# robot_board.net
KiCad netlist of a schematic drawn in EAGLE
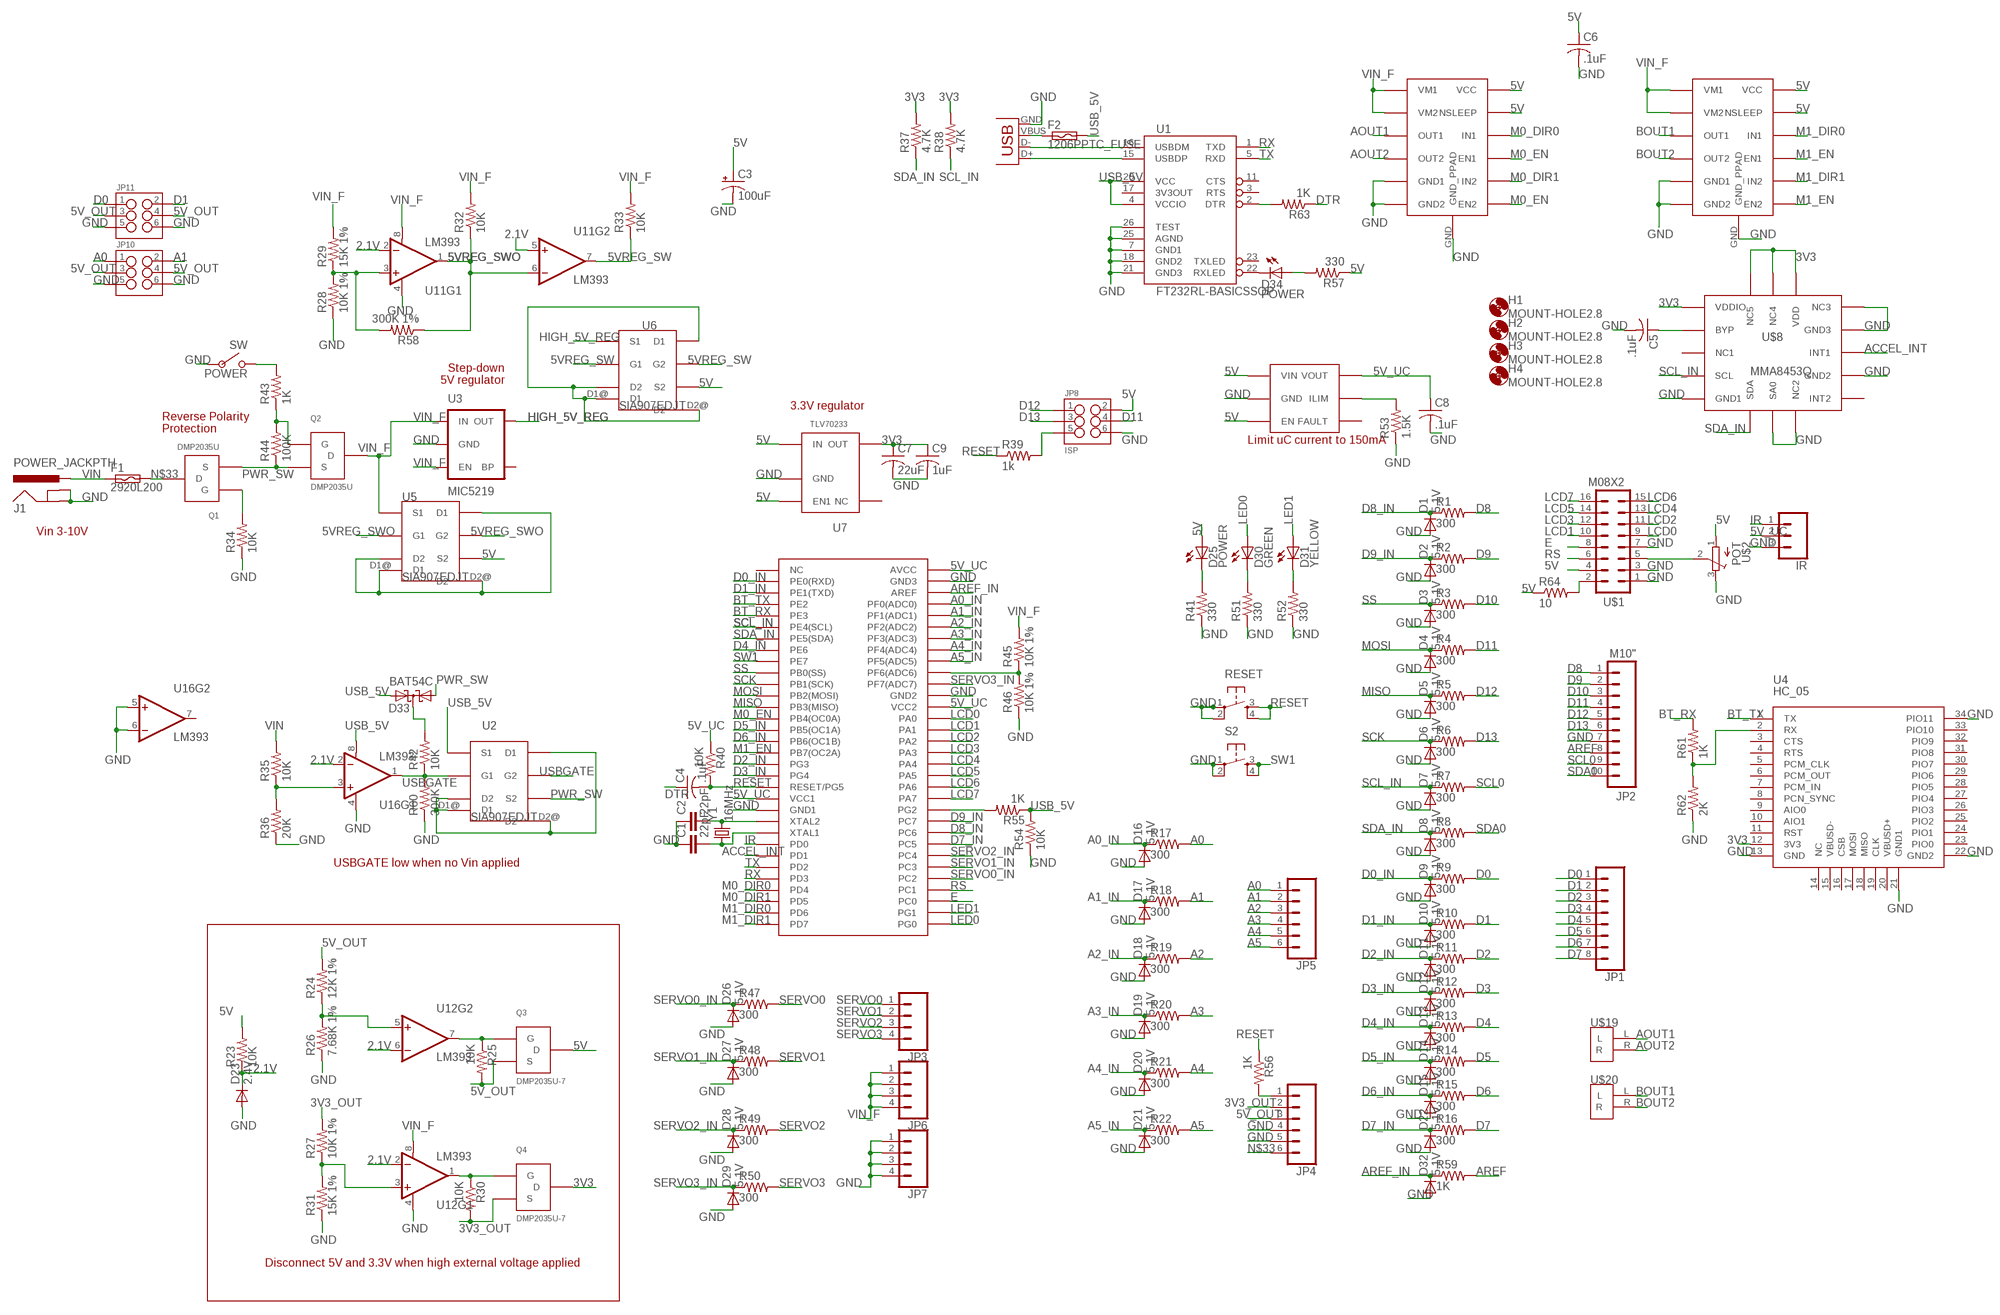
[diagram p0: schematic, sheet 1]

(export (version "E")
  (design (tool "Eeschema 10.0.6"))
  (components
    (comp (ref "C1")
      (value "22pF")
      (footprint "eagle-import:0805")
      (libsource (lib "eagle-import") (part "CAP0805"))
    )
    (comp (ref "C2")
      (value "22pF")
      (footprint "eagle-import:0805")
      (libsource (lib "eagle-import") (part "CAP0805"))
    )
    (comp (ref "C3")
      (value "100uF")
      (footprint "eagle-import:PANASONIC_D")
      (libsource (lib "eagle-import") (part "CAP_POLD"))
    )
    (comp (ref "C4")
      (value ".1uF")
      (footprint "eagle-import:C1206")
      (libsource (lib "eagle-import") (part "C-USC1206"))
    )
    (comp (ref "C5")
      (value ".1uF")
      (footprint "eagle-import:C1206")
      (libsource (lib "eagle-import") (part "C-USC1206"))
    )
    (comp (ref "C6")
      (value ".1uF")
      (footprint "eagle-import:C1206")
      (libsource (lib "eagle-import") (part "C-USC1206"))
    )
    (comp (ref "C7")
      (value "22uF")
      (footprint "eagle-import:C1206")
      (libsource (lib "eagle-import") (part "C-USC1206"))
    )
    (comp (ref "C8")
      (value ".1uF")
      (footprint "eagle-import:C1206")
      (libsource (lib "eagle-import") (part "C-USC1206"))
    )
    (comp (ref "C9")
      (value "1uF")
      (footprint "eagle-import:C1206")
      (libsource (lib "eagle-import") (part "C-USC1206"))
    )
    (comp (ref "D1")
      (value "5.1V")
      (footprint "eagle-import:SOT23-3")
      (libsource (lib "eagle-import") (part "DIODESOT23"))
    )
    (comp (ref "D2")
      (value "5.1V")
      (footprint "eagle-import:SOT23-3")
      (libsource (lib "eagle-import") (part "DIODESOT23"))
    )
    (comp (ref "D3")
      (value "5.1V")
      (footprint "eagle-import:SOT23-3")
      (libsource (lib "eagle-import") (part "DIODESOT23"))
    )
    (comp (ref "D4")
      (value "5.1V")
      (footprint "eagle-import:SOT23-3")
      (libsource (lib "eagle-import") (part "DIODESOT23"))
    )
    (comp (ref "D5")
      (value "5.1V")
      (footprint "eagle-import:SOT23-3")
      (libsource (lib "eagle-import") (part "DIODESOT23"))
    )
    (comp (ref "D6")
      (value "5.1V")
      (footprint "eagle-import:SOT23-3")
      (libsource (lib "eagle-import") (part "DIODESOT23"))
    )
    (comp (ref "D7")
      (value "5.1V")
      (footprint "eagle-import:SOT23-3")
      (libsource (lib "eagle-import") (part "DIODESOT23"))
    )
    (comp (ref "D8")
      (value "5.1V")
      (footprint "eagle-import:SOT23-3")
      (libsource (lib "eagle-import") (part "DIODESOT23"))
    )
    (comp (ref "D9")
      (value "5.1V")
      (footprint "eagle-import:SOT23-3")
      (libsource (lib "eagle-import") (part "DIODESOT23"))
    )
    (comp (ref "D10")
      (value "5.1V")
      (footprint "eagle-import:SOT23-3")
      (libsource (lib "eagle-import") (part "DIODESOT23"))
    )
    (comp (ref "D11")
      (value "5.1V")
      (footprint "eagle-import:SOT23-3")
      (libsource (lib "eagle-import") (part "DIODESOT23"))
    )
    (comp (ref "D12")
      (value "5.1V")
      (footprint "eagle-import:SOT23-3")
      (libsource (lib "eagle-import") (part "DIODESOT23"))
    )
    (comp (ref "D13")
      (value "5.1V")
      (footprint "eagle-import:SOT23-3")
      (libsource (lib "eagle-import") (part "DIODESOT23"))
    )
    (comp (ref "D14")
      (value "5.1V")
      (footprint "eagle-import:SOT23-3")
      (libsource (lib "eagle-import") (part "DIODESOT23"))
    )
    (comp (ref "D15")
      (value "5.1V")
      (footprint "eagle-import:SOT23-3")
      (libsource (lib "eagle-import") (part "DIODESOT23"))
    )
    (comp (ref "D16")
      (value "5.1V")
      (footprint "eagle-import:SOT23-3")
      (libsource (lib "eagle-import") (part "DIODESOT23"))
    )
    (comp (ref "D17")
      (value "5.1V")
      (footprint "eagle-import:SOT23-3")
      (libsource (lib "eagle-import") (part "DIODESOT23"))
    )
    (comp (ref "D18")
      (value "5.1V")
      (footprint "eagle-import:SOT23-3")
      (libsource (lib "eagle-import") (part "DIODESOT23"))
    )
    (comp (ref "D19")
      (value "5.1V")
      (footprint "eagle-import:SOT23-3")
      (libsource (lib "eagle-import") (part "DIODESOT23"))
    )
    (comp (ref "D20")
      (value "5.1V")
      (footprint "eagle-import:SOT23-3")
      (libsource (lib "eagle-import") (part "DIODESOT23"))
    )
    (comp (ref "D21")
      (value "5.1V")
      (footprint "eagle-import:SOT23-3")
      (libsource (lib "eagle-import") (part "DIODESOT23"))
    )
    (comp (ref "D22")
      (value "5.1V")
      (footprint "eagle-import:SOT23-3")
      (libsource (lib "eagle-import") (part "DIODESOT23"))
    )
    (comp (ref "D23")
      (value "2.4V")
      (footprint "eagle-import:SOT23-3")
      (libsource (lib "eagle-import") (part "DIODESOT23"))
    )
    (comp (ref "D25")
      (value "POWER")
      (footprint "eagle-import:LED-1206")
      (libsource (lib "eagle-import") (part "LED-GREENLILYPAD"))
    )
    (comp (ref "D26")
      (value "5.1V")
      (footprint "eagle-import:SOT23-3")
      (libsource (lib "eagle-import") (part "DIODESOT23"))
    )
    (comp (ref "D27")
      (value "5.1V")
      (footprint "eagle-import:SOT23-3")
      (libsource (lib "eagle-import") (part "DIODESOT23"))
    )
    (comp (ref "D28")
      (value "5.1V")
      (footprint "eagle-import:SOT23-3")
      (libsource (lib "eagle-import") (part "DIODESOT23"))
    )
    (comp (ref "D29")
      (value "5.1V")
      (footprint "eagle-import:SOT23-3")
      (libsource (lib "eagle-import") (part "DIODESOT23"))
    )
    (comp (ref "D30")
      (value "GREEN")
      (footprint "eagle-import:LED-1206")
      (libsource (lib "eagle-import") (part "LED-GREENLILYPAD"))
    )
    (comp (ref "D31")
      (value "YELLOW")
      (footprint "eagle-import:LED-1206")
      (libsource (lib "eagle-import") (part "LED-GREENLILYPAD"))
    )
    (comp (ref "D32")
      (value "5.1V")
      (footprint "eagle-import:SOT23-3")
      (libsource (lib "eagle-import") (part "DIODESOT23"))
    )
    (comp (ref "D33")
      (value "BAT54C")
      (footprint "eagle-import:SOT23")
      (libsource (lib "eagle-import") (part "BAT54C"))
    )
    (comp (ref "D34")
      (value "POWER")
      (footprint "eagle-import:LED-1206")
      (libsource (lib "eagle-import") (part "LED-GREENLILYPAD"))
    )
    (comp (ref "F1")
      (value "2920L200")
      (footprint "eagle-import:SMD050F")
      (libsource (lib "eagle-import") (part "2920L200"))
    )
    (comp (ref "F2")
      (value "1206PPTC_FUSE")
      (footprint "eagle-import:R1206")
      (libsource (lib "eagle-import") (part "1206PPTC_FUSE"))
    )
    (comp (ref "H1")
      (value "MOUNT-HOLE2.8")
      (footprint "eagle-import:2,8")
      (libsource (lib "eagle-import") (part "MOUNT-HOLE2.8"))
    )
    (comp (ref "H2")
      (value "MOUNT-HOLE2.8")
      (footprint "eagle-import:2,8")
      (libsource (lib "eagle-import") (part "MOUNT-HOLE2.8"))
    )
    (comp (ref "H3")
      (value "MOUNT-HOLE2.8")
      (footprint "eagle-import:2,8")
      (libsource (lib "eagle-import") (part "MOUNT-HOLE2.8"))
    )
    (comp (ref "H4")
      (value "MOUNT-HOLE2.8")
      (footprint "eagle-import:2,8")
      (libsource (lib "eagle-import") (part "MOUNT-HOLE2.8"))
    )
    (comp (ref "IR")
      (value "M03PTH")
      (footprint "eagle-import:1X03")
      (libsource (lib "eagle-import") (part "M03PTH"))
    )
    (comp (ref "J1")
      (value "POWER_JACKPTH")
      (footprint "eagle-import:POWER_JACK_PTH")
      (libsource (lib "eagle-import") (part "POWER_JACKPTH"))
    )
    (comp (ref "JP1")
      (value "M081X08")
      (footprint "eagle-import:1X08")
      (libsource (lib "eagle-import") (part "M081X08"))
    )
    (comp (ref "JP2")
      (value "M10\"")
      (footprint "eagle-import:1X10")
      (libsource (lib "eagle-import") (part "M10{dblquote}"))
    )
    (comp (ref "JP3")
      (value "M04PTH")
      (footprint "eagle-import:1X04")
      (libsource (lib "eagle-import") (part "M04PTH"))
    )
    (comp (ref "JP4")
      (value "M06SIP")
      (footprint "eagle-import:1X06")
      (libsource (lib "eagle-import") (part "M06SIP"))
    )
    (comp (ref "JP5")
      (value "M06SIP")
      (footprint "eagle-import:1X06")
      (libsource (lib "eagle-import") (part "M06SIP"))
    )
    (comp (ref "JP6")
      (value "M04PTH")
      (footprint "eagle-import:1X04")
      (libsource (lib "eagle-import") (part "M04PTH"))
    )
    (comp (ref "JP7")
      (value "M04PTH")
      (footprint "eagle-import:1X04")
      (libsource (lib "eagle-import") (part "M04PTH"))
    )
    (comp (ref "JP8")
      (value "ISP")
      (footprint "eagle-import:2X3")
      (libsource (lib "eagle-import") (part "M03X22X3_SILK_SM"))
    )
    (comp (ref "JP9")
      (value "USB-B")
      (footprint "eagle-import:USB-B-PTH")
      (libsource (lib "eagle-import") (part "USBPTH"))
    )
    (comp (ref "JP10")
      (value "M03X22X3_SILK_SM")
      (footprint "eagle-import:2X3")
      (libsource (lib "eagle-import") (part "M03X22X3_SILK_SM"))
    )
    (comp (ref "JP11")
      (value "M03X22X3_SILK_SM")
      (footprint "eagle-import:2X3")
      (libsource (lib "eagle-import") (part "M03X22X3_SILK_SM"))
    )
    (comp (ref "POWER")
      (value "SW")
      (footprint "eagle-import:SW")
      (libsource (lib "eagle-import") (part "SW"))
    )
    (comp (ref "Q1")
      (value "DMP2035U")
      (footprint "eagle-import:SOT23")
      (libsource (lib "eagle-import") (part "DMP2035U"))
    )
    (comp (ref "Q2")
      (value "DMP2035U")
      (footprint "eagle-import:SOT23")
      (libsource (lib "eagle-import") (part "DMP2035U"))
    )
    (comp (ref "Q3")
      (value "DMP2035U-7")
      (footprint "eagle-import:SOT23@1")
      (libsource (lib "eagle-import") (part "DMP2035U-7"))
    )
    (comp (ref "Q4")
      (value "DMP2035U-7")
      (footprint "eagle-import:SOT23@1")
      (libsource (lib "eagle-import") (part "DMP2035U-7"))
    )
    (comp (ref "R1")
      (value "300")
      (footprint "eagle-import:R1206")
      (libsource (lib "eagle-import") (part "R-US_R1206"))
    )
    (comp (ref "R2")
      (value "300")
      (footprint "eagle-import:R1206")
      (libsource (lib "eagle-import") (part "R-US_R1206"))
    )
    (comp (ref "R3")
      (value "300")
      (footprint "eagle-import:R1206")
      (libsource (lib "eagle-import") (part "R-US_R1206"))
    )
    (comp (ref "R4")
      (value "300")
      (footprint "eagle-import:R1206")
      (libsource (lib "eagle-import") (part "R-US_R1206"))
    )
    (comp (ref "R5")
      (value "300")
      (footprint "eagle-import:R1206")
      (libsource (lib "eagle-import") (part "R-US_R1206"))
    )
    (comp (ref "R6")
      (value "300")
      (footprint "eagle-import:R1206")
      (libsource (lib "eagle-import") (part "R-US_R1206"))
    )
    (comp (ref "R7")
      (value "300")
      (footprint "eagle-import:R1206")
      (libsource (lib "eagle-import") (part "R-US_R1206"))
    )
    (comp (ref "R8")
      (value "300")
      (footprint "eagle-import:R1206")
      (libsource (lib "eagle-import") (part "R-US_R1206"))
    )
    (comp (ref "R9")
      (value "300")
      (footprint "eagle-import:R1206")
      (libsource (lib "eagle-import") (part "R-US_R1206"))
    )
    (comp (ref "R10")
      (value "300")
      (footprint "eagle-import:R1206")
      (libsource (lib "eagle-import") (part "R-US_R1206"))
    )
    (comp (ref "R11")
      (value "300")
      (footprint "eagle-import:R1206")
      (libsource (lib "eagle-import") (part "R-US_R1206"))
    )
    (comp (ref "R12")
      (value "300")
      (footprint "eagle-import:R1206")
      (libsource (lib "eagle-import") (part "R-US_R1206"))
    )
    (comp (ref "R13")
      (value "300")
      (footprint "eagle-import:R1206")
      (libsource (lib "eagle-import") (part "R-US_R1206"))
    )
    (comp (ref "R14")
      (value "300")
      (footprint "eagle-import:R1206")
      (libsource (lib "eagle-import") (part "R-US_R1206"))
    )
    (comp (ref "R15")
      (value "300")
      (footprint "eagle-import:R1206")
      (libsource (lib "eagle-import") (part "R-US_R1206"))
    )
    (comp (ref "R16")
      (value "300")
      (footprint "eagle-import:R1206")
      (libsource (lib "eagle-import") (part "R-US_R1206"))
    )
    (comp (ref "R17")
      (value "300")
      (footprint "eagle-import:R1206")
      (libsource (lib "eagle-import") (part "R-US_R1206"))
    )
    (comp (ref "R18")
      (value "300")
      (footprint "eagle-import:R1206")
      (libsource (lib "eagle-import") (part "R-US_R1206"))
    )
    (comp (ref "R19")
      (value "300")
      (footprint "eagle-import:R1206")
      (libsource (lib "eagle-import") (part "R-US_R1206"))
    )
    (comp (ref "R20")
      (value "300")
      (footprint "eagle-import:R1206")
      (libsource (lib "eagle-import") (part "R-US_R1206"))
    )
    (comp (ref "R21")
      (value "300")
      (footprint "eagle-import:R1206")
      (libsource (lib "eagle-import") (part "R-US_R1206"))
    )
    (comp (ref "R22")
      (value "300")
      (footprint "eagle-import:R1206")
      (libsource (lib "eagle-import") (part "R-US_R1206"))
    )
    (comp (ref "R23")
      (value "10K")
      (footprint "eagle-import:R1206")
      (libsource (lib "eagle-import") (part "R-US_R1206"))
    )
    (comp (ref "R24")
      (value "12K 1%")
      (footprint "eagle-import:R1206")
      (libsource (lib "eagle-import") (part "R-US_R1206"))
    )
    (comp (ref "R25")
      (value "10K")
      (footprint "eagle-import:R1206")
      (libsource (lib "eagle-import") (part "R-US_R1206"))
    )
    (comp (ref "R26")
      (value "7.68K 1%")
      (footprint "eagle-import:R1206")
      (libsource (lib "eagle-import") (part "R-US_R1206"))
    )
    (comp (ref "R27")
      (value "10K 1%")
      (footprint "eagle-import:R1206")
      (libsource (lib "eagle-import") (part "R-US_R1206"))
    )
    (comp (ref "R28")
      (value "10K 1%")
      (footprint "eagle-import:R1206")
      (libsource (lib "eagle-import") (part "R-US_R1206"))
    )
    (comp (ref "R29")
      (value "15K 1%")
      (footprint "eagle-import:R1206")
      (libsource (lib "eagle-import") (part "R-US_R1206"))
    )
    (comp (ref "R30")
      (value "10K")
      (footprint "eagle-import:R1206")
      (libsource (lib "eagle-import") (part "R-US_R1206"))
    )
    (comp (ref "R31")
      (value "15K 1%")
      (footprint "eagle-import:R1206")
      (libsource (lib "eagle-import") (part "R-US_R1206"))
    )
    (comp (ref "R32")
      (value "10K")
      (footprint "eagle-import:R1206")
      (libsource (lib "eagle-import") (part "R-US_R1206"))
    )
    (comp (ref "R33")
      (value "10K")
      (footprint "eagle-import:R1206")
      (libsource (lib "eagle-import") (part "R-US_R1206"))
    )
    (comp (ref "R34")
      (value "10K")
      (footprint "eagle-import:R1206")
      (libsource (lib "eagle-import") (part "R-US_R1206"))
    )
    (comp (ref "R35")
      (value "10K")
      (footprint "eagle-import:R1206")
      (libsource (lib "eagle-import") (part "R-US_R1206"))
    )
    (comp (ref "R36")
      (value "20K")
      (footprint "eagle-import:R1206")
      (libsource (lib "eagle-import") (part "R-US_R1206"))
    )
    (comp (ref "R37")
      (value "4.7K")
      (footprint "eagle-import:R1206")
      (libsource (lib "eagle-import") (part "R-US_R1206"))
    )
    (comp (ref "R38")
      (value "4.7K")
      (footprint "eagle-import:R1206")
      (libsource (lib "eagle-import") (part "R-US_R1206"))
    )
    (comp (ref "R39")
      (value "1k")
      (footprint "eagle-import:R1206")
      (libsource (lib "eagle-import") (part "R-US_R1206"))
    )
    (comp (ref "R40")
      (value "10K")
      (footprint "eagle-import:R1206")
      (libsource (lib "eagle-import") (part "R-US_R1206"))
    )
    (comp (ref "R41")
      (value "330")
      (footprint "eagle-import:R1206")
      (libsource (lib "eagle-import") (part "R-US_R1206"))
    )
    (comp (ref "R42")
      (value "10K")
      (footprint "eagle-import:R1206")
      (libsource (lib "eagle-import") (part "R-US_R1206"))
    )
    (comp (ref "R43")
      (value "1K")
      (footprint "eagle-import:R1206")
      (libsource (lib "eagle-import") (part "R-US_R1206"))
    )
    (comp (ref "R44")
      (value "100K")
      (footprint "eagle-import:R1206")
      (libsource (lib "eagle-import") (part "R-US_R1206"))
    )
    (comp (ref "R45")
      (value "10K 1%")
      (footprint "eagle-import:R1206")
      (libsource (lib "eagle-import") (part "R-US_R1206"))
    )
    (comp (ref "R46")
      (value "10K 1%")
      (footprint "eagle-import:R1206")
      (libsource (lib "eagle-import") (part "R-US_R1206"))
    )
    (comp (ref "R47")
      (value "300")
      (footprint "eagle-import:R1206")
      (libsource (lib "eagle-import") (part "R-US_R1206"))
    )
    (comp (ref "R48")
      (value "300")
      (footprint "eagle-import:R1206")
      (libsource (lib "eagle-import") (part "R-US_R1206"))
    )
    (comp (ref "R49")
      (value "300")
      (footprint "eagle-import:R1206")
      (libsource (lib "eagle-import") (part "R-US_R1206"))
    )
    (comp (ref "R50")
      (value "300")
      (footprint "eagle-import:R1206")
      (libsource (lib "eagle-import") (part "R-US_R1206"))
    )
    (comp (ref "R51")
      (value "330")
      (footprint "eagle-import:R1206")
      (libsource (lib "eagle-import") (part "R-US_R1206"))
    )
    (comp (ref "R52")
      (value "330")
      (footprint "eagle-import:R1206")
      (libsource (lib "eagle-import") (part "R-US_R1206"))
    )
    (comp (ref "R53")
      (value "1.5K")
      (footprint "eagle-import:R1206")
      (libsource (lib "eagle-import") (part "R-US_R1206"))
    )
    (comp (ref "R54")
      (value "10K")
      (footprint "eagle-import:R1206")
      (libsource (lib "eagle-import") (part "R-US_R1206"))
    )
    (comp (ref "R55")
      (value "1K")
      (footprint "eagle-import:R1206")
      (libsource (lib "eagle-import") (part "R-US_R1206"))
    )
    (comp (ref "R56")
      (value "1K")
      (footprint "eagle-import:R1206")
      (libsource (lib "eagle-import") (part "R-US_R1206"))
    )
    (comp (ref "R57")
      (value "330")
      (footprint "eagle-import:R1206")
      (libsource (lib "eagle-import") (part "R-US_R1206"))
    )
    (comp (ref "R58")
      (value "300K 1%")
      (footprint "eagle-import:R1206")
      (libsource (lib "eagle-import") (part "R-US_R1206"))
    )
    (comp (ref "R59")
      (value "1K")
      (footprint "eagle-import:R1206")
      (libsource (lib "eagle-import") (part "R-US_R1206"))
    )
    (comp (ref "R60")
      (value "300K")
      (footprint "eagle-import:R1206")
      (libsource (lib "eagle-import") (part "R-US_R1206"))
    )
    (comp (ref "R61")
      (value "1K")
      (footprint "eagle-import:R1206")
      (libsource (lib "eagle-import") (part "R-US_R1206"))
    )
    (comp (ref "R62")
      (value "2K")
      (footprint "eagle-import:R1206")
      (libsource (lib "eagle-import") (part "R-US_R1206"))
    )
    (comp (ref "R63")
      (value "1K")
      (footprint "eagle-import:R1206")
      (libsource (lib "eagle-import") (part "R-US_R1206"))
    )
    (comp (ref "R64")
      (value "10")
      (footprint "eagle-import:R1206")
      (libsource (lib "eagle-import") (part "R-US_R1206"))
    )
    (comp (ref "RESET")
      (value "TAC_SWITCHPTH")
      (footprint "eagle-import:TACTILE-PTH")
      (libsource (lib "eagle-import") (part "TAC_SWITCHPTH"))
    )
    (comp (ref "S2")
      (value "TAC_SWITCHPTH")
      (footprint "eagle-import:TACTILE-PTH")
      (libsource (lib "eagle-import") (part "TAC_SWITCHPTH"))
    )
    (comp (ref "U$1")
      (value "M08X2")
      (footprint "eagle-import:2X8")
      (libsource (lib "eagle-import") (part "M08X2"))
    )
    (comp (ref "U$2")
      (value "POT")
      (footprint "eagle-import:POT")
      (libsource (lib "eagle-import") (part "POT"))
    )
    (comp (ref "U$8")
      (value "MMA8453Q")
      (footprint "eagle-import:QFN-COL")
      (libsource (lib "eagle-import") (part "MMA8453Q"))
    )
    (comp (ref "U$19")
      (value "2POS_TERMINAL")
      (footprint "eagle-import:2POS_TERMINAL")
      (libsource (lib "eagle-import") (part "2POS_TERMINAL"))
    )
    (comp (ref "U$20")
      (value "2POS_TERMINAL")
      (footprint "eagle-import:2POS_TERMINAL")
      (libsource (lib "eagle-import") (part "2POS_TERMINAL"))
    )
    (comp (ref "U1")
      (value "FT232RL-BASICSSOP")
      (footprint "eagle-import:SSOP28DB")
      (libsource (lib "eagle-import") (part "FT232RL-BASICSSOP"))
    )
    (comp (ref "U2")
      (value "SIA907EDJT")
      (footprint "eagle-import:SC70T")
      (libsource (lib "eagle-import") (part "SIA907EDJT"))
    )
    (comp (ref "U3")
      (value "MIC5219")
      (footprint "eagle-import:SOT23-5")
      (libsource (lib "eagle-import") (part "MIC52055V"))
    )
    (comp (ref "U4")
      (value "HC_05")
      (footprint "eagle-import:BLUETOOTH_SMD")
      (libsource (lib "eagle-import") (part "HC_05"))
    )
    (comp (ref "U5")
      (value "SIA907EDJT")
      (footprint "eagle-import:SC70T")
      (libsource (lib "eagle-import") (part "SIA907EDJT"))
    )
    (comp (ref "U6")
      (value "SIA907EDJT")
      (footprint "eagle-import:SC70T")
      (libsource (lib "eagle-import") (part "SIA907EDJT"))
    )
    (comp (ref "U7")
      (value "TLV70233")
      (footprint "eagle-import:SOT-23-5")
      (libsource (lib "eagle-import") (part "TLV70233"))
    )
    (comp (ref "U8")
      (value "MIC2009A")
      (footprint "eagle-import:SOT23-M5")
      (libsource (lib "eagle-import") (part "MIC2009A"))
    )
    (comp (ref "U9")
      (value "DRV8839")
      (footprint "eagle-import:PWSON-N12")
      (libsource (lib "eagle-import") (part "DRV8839"))
    )
    (comp (ref "U10")
      (value "DRV8839")
      (footprint "eagle-import:PWSON-N12")
      (libsource (lib "eagle-import") (part "DRV8839"))
    )
    (comp (ref "U11")
      (value "LM393")
      (footprint "eagle-import:SO08")
      (libsource (lib "eagle-import") (part "LM393"))
    )
    (comp (ref "U12")
      (value "LM393")
      (footprint "eagle-import:SO08")
      (libsource (lib "eagle-import") (part "LM393"))
    )
    (comp (ref "U16")
      (value "LM393")
      (footprint "eagle-import:SO08")
      (libsource (lib "eagle-import") (part "LM393"))
    )
    (comp (ref "U17")
      (value "ATMEGA325PA")
      (footprint "eagle-import:TQFP64")
      (libsource (lib "eagle-import") (part "ATMEGA325PA"))
    )
    (comp (ref "Y1")
      (value "16MHz")
      (footprint "eagle-import:CRYSTAL-SMD-10.5X4.8-2PIN")
      (libsource (lib "eagle-import") (part "CRYSTAL10.5X4.8"))
    )
  )
  (nets
    (net (code "1") (name "/2.1V") (class "Default")
      (node (ref "D23") (pin "3") (pinfunction "C_3") (pintype "passive"))
      (node (ref "R23") (pin "1") (pinfunction "1_1") (pintype "passive"))
      (node (ref "U11") (pin "2") (pinfunction "-IN_2") (pintype "input"))
      (node (ref "U11") (pin "5") (pinfunction "+IN_5") (pintype "input"))
      (node (ref "U12") (pin "2") (pinfunction "-IN_2") (pintype "input"))
      (node (ref "U12") (pin "6") (pinfunction "-IN_6") (pintype "input"))
      (node (ref "U16") (pin "2") (pinfunction "-IN_2") (pintype "input"))
    )
    (net (code "2") (name "/3V3") (class "Default")
      (node (ref "C7") (pin "1") (pinfunction "1_1") (pintype "passive"))
      (node (ref "C9") (pin "1") (pinfunction "1_1") (pintype "passive"))
      (node (ref "Q4") (pin "3") (pinfunction "D_3") (pintype "bidirectional"))
      (node (ref "R37") (pin "2") (pinfunction "2_2") (pintype "passive"))
      (node (ref "R38") (pin "2") (pinfunction "2_2") (pintype "passive"))
      (node (ref "U$8") (pin "P$1") (pinfunction "VDDIO_P$1") (pintype "bidirectional"))
      (node (ref "U$8") (pin "P$14") (pinfunction "VDD_P$14") (pintype "bidirectional"))
      (node (ref "U$8") (pin "P$15") (pinfunction "NC4_P$15") (pintype "bidirectional"))
      (node (ref "U$8") (pin "P$16") (pinfunction "NC5_P$16") (pintype "bidirectional"))
      (node (ref "U4") (pin "12") (pinfunction "3V3_12") (pintype "bidirectional"))
      (node (ref "U7") (pin "P$4") (pinfunction "OUT_P$4") (pintype "bidirectional"))
    )
    (net (code "3") (name "/3V3_OUT") (class "Default")
      (node (ref "JP4") (pin "2") (pinfunction "2_2") (pintype "passive"))
      (node (ref "Q4") (pin "2") (pinfunction "S_2") (pintype "bidirectional"))
      (node (ref "R27") (pin "2") (pinfunction "2_2") (pintype "passive"))
      (node (ref "R30") (pin "2") (pinfunction "2_2") (pintype "passive"))
    )
    (net (code "4") (name "/5V") (class "Default")
      (node (ref "C3") (pin "+") (pinfunction "+_+") (pintype "passive"))
      (node (ref "C6") (pin "1") (pinfunction "1_1") (pintype "passive"))
      (node (ref "D25") (pin "A") (pinfunction "A_A") (pintype "passive"))
      (node (ref "JP8") (pin "2") (pinfunction "2_2") (pintype "bidirectional"))
      (node (ref "Q3") (pin "3") (pinfunction "D_3") (pintype "bidirectional"))
      (node (ref "R23") (pin "2") (pinfunction "2_2") (pintype "passive"))
      (node (ref "R57") (pin "1") (pinfunction "1_1") (pintype "passive"))
      (node (ref "R64") (pin "1") (pinfunction "1_1") (pintype "passive"))
      (node (ref "U$1") (pin "4") (pinfunction "4_4") (pintype "passive"))
      (node (ref "U$2") (pin "1") (pinfunction "A_1") (pintype "passive"))
      (node (ref "U10") (pin "P$7") (pinfunction "VCC_P$7") (pintype "bidirectional"))
      (node (ref "U10") (pin "P$8") (pinfunction "NSLEEP_P$8") (pintype "bidirectional"))
      (node (ref "U5") (pin "S2") (pinfunction "S2_S2") (pintype "bidirectional"))
      (node (ref "U6") (pin "S2") (pinfunction "S2_S2") (pintype "bidirectional"))
      (node (ref "U7") (pin "P$1") (pinfunction "IN_P$1") (pintype "bidirectional"))
      (node (ref "U7") (pin "P$3") (pinfunction "EN1_P$3") (pintype "bidirectional"))
      (node (ref "U8") (pin "P$1") (pinfunction "VIN_P$1") (pintype "bidirectional"))
      (node (ref "U8") (pin "P$3") (pinfunction "EN_P$3") (pintype "bidirectional"))
      (node (ref "U9") (pin "P$7") (pinfunction "VCC_P$7") (pintype "bidirectional"))
      (node (ref "U9") (pin "P$8") (pinfunction "NSLEEP_P$8") (pintype "bidirectional"))
    )
    (net (code "5") (name "/5VREG_SW") (class "Default")
      (node (ref "R33") (pin "1") (pinfunction "1_1") (pintype "passive"))
      (node (ref "U11") (pin "7") (pinfunction "OUT_7") (pintype "output"))
      (node (ref "U6") (pin "G1") (pinfunction "G1_G1") (pintype "bidirectional"))
      (node (ref "U6") (pin "G2") (pinfunction "G2_G2") (pintype "bidirectional"))
    )
    (net (code "6") (name "/5VREG_SWO") (class "Default")
      (node (ref "R32") (pin "1") (pinfunction "1_1") (pintype "passive"))
      (node (ref "R58") (pin "1") (pinfunction "1_1") (pintype "passive"))
      (node (ref "U11") (pin "1") (pinfunction "OUT_1") (pintype "output"))
      (node (ref "U11") (pin "6") (pinfunction "-IN_6") (pintype "input"))
      (node (ref "U5") (pin "G1") (pinfunction "G1_G1") (pintype "bidirectional"))
      (node (ref "U5") (pin "G2") (pinfunction "G2_G2") (pintype "bidirectional"))
    )
    (net (code "7") (name "/5V_OUT") (class "Default")
      (node (ref "JP10") (pin "3") (pinfunction "3_3") (pintype "bidirectional"))
      (node (ref "JP10") (pin "4") (pinfunction "4_4") (pintype "bidirectional"))
      (node (ref "JP11") (pin "3") (pinfunction "3_3") (pintype "bidirectional"))
      (node (ref "JP11") (pin "4") (pinfunction "4_4") (pintype "bidirectional"))
      (node (ref "JP4") (pin "3") (pinfunction "3_3") (pintype "passive"))
      (node (ref "Q3") (pin "2") (pinfunction "S_2") (pintype "bidirectional"))
      (node (ref "R24") (pin "2") (pinfunction "2_2") (pintype "passive"))
      (node (ref "R25") (pin "2") (pinfunction "2_2") (pintype "passive"))
    )
    (net (code "8") (name "/5V_UC") (class "Default")
      (node (ref "C8") (pin "1") (pinfunction "1_1") (pintype "passive"))
      (node (ref "IR") (pin "2") (pinfunction "2_2") (pintype "passive"))
      (node (ref "R40") (pin "1") (pinfunction "1_1") (pintype "passive"))
      (node (ref "U17") (pin "21") (pinfunction "VCC1_21") (pintype "bidirectional"))
      (node (ref "U17") (pin "52") (pinfunction "VCC2_52") (pintype "bidirectional"))
      (node (ref "U17") (pin "64") (pinfunction "AVCC_64") (pintype "bidirectional"))
      (node (ref "U8") (pin "P$6") (pinfunction "VOUT_P$6") (pintype "bidirectional"))
    )
    (net (code "9") (name "/A0") (class "Default")
      (node (ref "JP10") (pin "1") (pinfunction "1_1") (pintype "bidirectional"))
      (node (ref "JP5") (pin "1") (pinfunction "1_1") (pintype "passive"))
      (node (ref "R17") (pin "2") (pinfunction "2_2") (pintype "passive"))
    )
    (net (code "10") (name "/A0_IN") (class "Default")
      (node (ref "D16") (pin "3") (pinfunction "C_3") (pintype "passive"))
      (node (ref "R17") (pin "1") (pinfunction "1_1") (pintype "passive"))
      (node (ref "U17") (pin "61") (pinfunction "PF0(ADC0)_61") (pintype "bidirectional"))
    )
    (net (code "11") (name "/A1") (class "Default")
      (node (ref "JP10") (pin "2") (pinfunction "2_2") (pintype "bidirectional"))
      (node (ref "JP5") (pin "2") (pinfunction "2_2") (pintype "passive"))
      (node (ref "R18") (pin "2") (pinfunction "2_2") (pintype "passive"))
    )
    (net (code "12") (name "/A1_IN") (class "Default")
      (node (ref "D17") (pin "3") (pinfunction "C_3") (pintype "passive"))
      (node (ref "R18") (pin "1") (pinfunction "1_1") (pintype "passive"))
      (node (ref "U17") (pin "60") (pinfunction "PF1(ADC1)_60") (pintype "bidirectional"))
    )
    (net (code "13") (name "/A2") (class "Default")
      (node (ref "JP5") (pin "3") (pinfunction "3_3") (pintype "passive"))
      (node (ref "R19") (pin "2") (pinfunction "2_2") (pintype "passive"))
    )
    (net (code "14") (name "/A2_IN") (class "Default")
      (node (ref "D18") (pin "3") (pinfunction "C_3") (pintype "passive"))
      (node (ref "R19") (pin "1") (pinfunction "1_1") (pintype "passive"))
      (node (ref "U17") (pin "59") (pinfunction "PF2(ADC2)_59") (pintype "bidirectional"))
    )
    (net (code "15") (name "/A3") (class "Default")
      (node (ref "JP5") (pin "4") (pinfunction "4_4") (pintype "passive"))
      (node (ref "R20") (pin "2") (pinfunction "2_2") (pintype "passive"))
    )
    (net (code "16") (name "/A3_IN") (class "Default")
      (node (ref "D19") (pin "3") (pinfunction "C_3") (pintype "passive"))
      (node (ref "R20") (pin "1") (pinfunction "1_1") (pintype "passive"))
      (node (ref "U17") (pin "58") (pinfunction "PF3(ADC3)_58") (pintype "bidirectional"))
    )
    (net (code "17") (name "/A4") (class "Default")
      (node (ref "JP5") (pin "5") (pinfunction "5_5") (pintype "passive"))
      (node (ref "R21") (pin "2") (pinfunction "2_2") (pintype "passive"))
    )
    (net (code "18") (name "/A4_IN") (class "Default")
      (node (ref "D20") (pin "3") (pinfunction "C_3") (pintype "passive"))
      (node (ref "R21") (pin "1") (pinfunction "1_1") (pintype "passive"))
      (node (ref "U17") (pin "57") (pinfunction "PF4(ADC4)_57") (pintype "bidirectional"))
    )
    (net (code "19") (name "/A5") (class "Default")
      (node (ref "JP5") (pin "6") (pinfunction "6_6") (pintype "passive"))
      (node (ref "R22") (pin "2") (pinfunction "2_2") (pintype "passive"))
    )
    (net (code "20") (name "/A5_IN") (class "Default")
      (node (ref "D21") (pin "3") (pinfunction "C_3") (pintype "passive"))
      (node (ref "R22") (pin "1") (pinfunction "1_1") (pintype "passive"))
      (node (ref "U17") (pin "56") (pinfunction "PF5(ADC5)_56") (pintype "bidirectional"))
    )
    (net (code "21") (name "/ACCEL_INT") (class "Default")
      (node (ref "U$8") (pin "P$11") (pinfunction "INT1_P$11") (pintype "bidirectional"))
      (node (ref "U17") (pin "26") (pinfunction "PD1_26") (pintype "bidirectional"))
    )
    (net (code "22") (name "/AOUT1") (class "Default")
      (node (ref "U$19") (pin "L") (pinfunction "L_L") (pintype "bidirectional"))
      (node (ref "U9") (pin "P$3") (pinfunction "OUT1_P$3") (pintype "bidirectional"))
    )
    (net (code "23") (name "/AOUT2") (class "Default")
      (node (ref "U$19") (pin "R") (pinfunction "R_R") (pintype "bidirectional"))
      (node (ref "U9") (pin "P$4") (pinfunction "OUT2_P$4") (pintype "bidirectional"))
    )
    (net (code "24") (name "/AREF") (class "Default")
      (node (ref "JP2") (pin "8") (pinfunction "8_8") (pintype "passive"))
      (node (ref "R59") (pin "2") (pinfunction "2_2") (pintype "passive"))
    )
    (net (code "25") (name "/AREF_IN") (class "Default")
      (node (ref "D32") (pin "3") (pinfunction "C_3") (pintype "passive"))
      (node (ref "R59") (pin "1") (pinfunction "1_1") (pintype "passive"))
      (node (ref "U17") (pin "62") (pinfunction "AREF_62") (pintype "bidirectional"))
    )
    (net (code "26") (name "/BOUT1") (class "Default")
      (node (ref "U$20") (pin "L") (pinfunction "L_L") (pintype "bidirectional"))
      (node (ref "U10") (pin "P$3") (pinfunction "OUT1_P$3") (pintype "bidirectional"))
    )
    (net (code "27") (name "/BOUT2") (class "Default")
      (node (ref "U$20") (pin "R") (pinfunction "R_R") (pintype "bidirectional"))
      (node (ref "U10") (pin "P$4") (pinfunction "OUT2_P$4") (pintype "bidirectional"))
    )
    (net (code "28") (name "/BT_RX") (class "Default")
      (node (ref "R61") (pin "2") (pinfunction "2_2") (pintype "passive"))
      (node (ref "U17") (pin "5") (pinfunction "PE3_5") (pintype "bidirectional"))
    )
    (net (code "29") (name "/BT_TX") (class "Default")
      (node (ref "U17") (pin "4") (pinfunction "PE2_4") (pintype "bidirectional"))
      (node (ref "U4") (pin "1") (pinfunction "TX_1") (pintype "bidirectional"))
    )
    (net (code "30") (name "/D0") (class "Default")
      (node (ref "JP1") (pin "1") (pinfunction "1_1") (pintype "passive"))
      (node (ref "JP11") (pin "1") (pinfunction "1_1") (pintype "bidirectional"))
      (node (ref "R9") (pin "2") (pinfunction "2_2") (pintype "passive"))
    )
    (net (code "31") (name "/D0_IN") (class "Default")
      (node (ref "D9") (pin "3") (pinfunction "C_3") (pintype "passive"))
      (node (ref "R9") (pin "1") (pinfunction "1_1") (pintype "passive"))
      (node (ref "U17") (pin "2") (pinfunction "PE0(RXD)_2") (pintype "bidirectional"))
    )
    (net (code "32") (name "/D1") (class "Default")
      (node (ref "JP1") (pin "2") (pinfunction "2_2") (pintype "passive"))
      (node (ref "JP11") (pin "2") (pinfunction "2_2") (pintype "bidirectional"))
      (node (ref "R10") (pin "2") (pinfunction "2_2") (pintype "passive"))
    )
    (net (code "33") (name "/D1_IN") (class "Default")
      (node (ref "D10") (pin "3") (pinfunction "C_3") (pintype "passive"))
      (node (ref "R10") (pin "1") (pinfunction "1_1") (pintype "passive"))
      (node (ref "U17") (pin "3") (pinfunction "PE1(TXD)_3") (pintype "bidirectional"))
    )
    (net (code "34") (name "/D2") (class "Default")
      (node (ref "JP1") (pin "3") (pinfunction "3_3") (pintype "passive"))
      (node (ref "R11") (pin "2") (pinfunction "2_2") (pintype "passive"))
    )
    (net (code "35") (name "/D2_IN") (class "Default")
      (node (ref "D11") (pin "3") (pinfunction "C_3") (pintype "passive"))
      (node (ref "R11") (pin "1") (pinfunction "1_1") (pintype "passive"))
      (node (ref "U17") (pin "18") (pinfunction "PG3_18") (pintype "bidirectional"))
    )
    (net (code "36") (name "/D3") (class "Default")
      (node (ref "JP1") (pin "4") (pinfunction "4_4") (pintype "passive"))
      (node (ref "R12") (pin "2") (pinfunction "2_2") (pintype "passive"))
    )
    (net (code "37") (name "/D3_IN") (class "Default")
      (node (ref "D12") (pin "3") (pinfunction "C_3") (pintype "passive"))
      (node (ref "R12") (pin "1") (pinfunction "1_1") (pintype "passive"))
      (node (ref "U17") (pin "19") (pinfunction "PG4_19") (pintype "bidirectional"))
    )
    (net (code "38") (name "/D4") (class "Default")
      (node (ref "JP1") (pin "5") (pinfunction "5_5") (pintype "passive"))
      (node (ref "R13") (pin "2") (pinfunction "2_2") (pintype "passive"))
    )
    (net (code "39") (name "/D4_IN") (class "Default")
      (node (ref "D13") (pin "3") (pinfunction "C_3") (pintype "passive"))
      (node (ref "R13") (pin "1") (pinfunction "1_1") (pintype "passive"))
      (node (ref "U17") (pin "8") (pinfunction "PE6_8") (pintype "bidirectional"))
    )
    (net (code "40") (name "/D5") (class "Default")
      (node (ref "JP1") (pin "6") (pinfunction "6_6") (pintype "passive"))
      (node (ref "R14") (pin "2") (pinfunction "2_2") (pintype "passive"))
    )
    (net (code "41") (name "/D5_IN") (class "Default")
      (node (ref "D14") (pin "3") (pinfunction "C_3") (pintype "passive"))
      (node (ref "R14") (pin "1") (pinfunction "1_1") (pintype "passive"))
      (node (ref "U17") (pin "15") (pinfunction "PB5(OC1A)_15") (pintype "bidirectional"))
    )
    (net (code "42") (name "/D6") (class "Default")
      (node (ref "JP1") (pin "7") (pinfunction "7_7") (pintype "passive"))
      (node (ref "R15") (pin "2") (pinfunction "2_2") (pintype "passive"))
    )
    (net (code "43") (name "/D6_IN") (class "Default")
      (node (ref "D15") (pin "3") (pinfunction "C_3") (pintype "passive"))
      (node (ref "R15") (pin "1") (pinfunction "1_1") (pintype "passive"))
      (node (ref "U17") (pin "16") (pinfunction "PB6(OC1B)_16") (pintype "bidirectional"))
    )
    (net (code "44") (name "/D7") (class "Default")
      (node (ref "JP1") (pin "8") (pinfunction "8_8") (pintype "passive"))
      (node (ref "R16") (pin "2") (pinfunction "2_2") (pintype "passive"))
    )
    (net (code "45") (name "/D7_IN") (class "Default")
      (node (ref "D22") (pin "3") (pinfunction "C_3") (pintype "passive"))
      (node (ref "R16") (pin "1") (pinfunction "1_1") (pintype "passive"))
      (node (ref "U17") (pin "40") (pinfunction "PC5_40") (pintype "bidirectional"))
    )
    (net (code "46") (name "/D8") (class "Default")
      (node (ref "JP2") (pin "1") (pinfunction "1_1") (pintype "passive"))
      (node (ref "R1") (pin "2") (pinfunction "2_2") (pintype "passive"))
    )
    (net (code "47") (name "/D8_IN") (class "Default")
      (node (ref "D1") (pin "3") (pinfunction "C_3") (pintype "passive"))
      (node (ref "R1") (pin "1") (pinfunction "1_1") (pintype "passive"))
      (node (ref "U17") (pin "41") (pinfunction "PC6_41") (pintype "bidirectional"))
    )
    (net (code "48") (name "/D9") (class "Default")
      (node (ref "JP2") (pin "2") (pinfunction "2_2") (pintype "passive"))
      (node (ref "R2") (pin "2") (pinfunction "2_2") (pintype "passive"))
    )
    (net (code "49") (name "/D9_IN") (class "Default")
      (node (ref "D2") (pin "3") (pinfunction "C_3") (pintype "passive"))
      (node (ref "R2") (pin "1") (pinfunction "1_1") (pintype "passive"))
      (node (ref "U17") (pin "42") (pinfunction "PC7_42") (pintype "bidirectional"))
    )
    (net (code "50") (name "/D10") (class "Default")
      (node (ref "JP2") (pin "3") (pinfunction "3_3") (pintype "passive"))
      (node (ref "R3") (pin "2") (pinfunction "2_2") (pintype "passive"))
    )
    (net (code "51") (name "/D11") (class "Default")
      (node (ref "JP2") (pin "4") (pinfunction "4_4") (pintype "passive"))
      (node (ref "JP8") (pin "4") (pinfunction "4_4") (pintype "bidirectional"))
      (node (ref "R4") (pin "2") (pinfunction "2_2") (pintype "passive"))
    )
    (net (code "52") (name "/D12") (class "Default")
      (node (ref "JP2") (pin "5") (pinfunction "5_5") (pintype "passive"))
      (node (ref "JP8") (pin "1") (pinfunction "1_1") (pintype "bidirectional"))
      (node (ref "R5") (pin "2") (pinfunction "2_2") (pintype "passive"))
    )
    (net (code "53") (name "/D13") (class "Default")
      (node (ref "JP2") (pin "6") (pinfunction "6_6") (pintype "passive"))
      (node (ref "JP8") (pin "3") (pinfunction "3_3") (pintype "bidirectional"))
      (node (ref "R6") (pin "2") (pinfunction "2_2") (pintype "passive"))
    )
    (net (code "54") (name "/DTR") (class "Default")
      (node (ref "C4") (pin "1") (pinfunction "1_1") (pintype "passive"))
      (node (ref "R63") (pin "1") (pinfunction "1_1") (pintype "passive"))
    )
    (net (code "55") (name "/E") (class "Default")
      (node (ref "U$1") (pin "8") (pinfunction "8_8") (pintype "passive"))
      (node (ref "U17") (pin "35") (pinfunction "PC0_35") (pintype "bidirectional"))
    )
    (net (code "56") (name "/GND") (class "Default")
      (node (ref "C1") (pin "1") (pinfunction "1_1") (pintype "passive"))
      (node (ref "C2") (pin "1") (pinfunction "1_1") (pintype "passive"))
      (node (ref "C3") (pin "-") (pinfunction "-_-") (pintype "passive"))
      (node (ref "C5") (pin "2") (pinfunction "2_2") (pintype "passive"))
      (node (ref "C6") (pin "2") (pinfunction "2_2") (pintype "passive"))
      (node (ref "C7") (pin "2") (pinfunction "2_2") (pintype "passive"))
      (node (ref "C8") (pin "2") (pinfunction "2_2") (pintype "passive"))
      (node (ref "C9") (pin "2") (pinfunction "2_2") (pintype "passive"))
      (node (ref "D1") (pin "1") (pinfunction "A_1") (pintype "passive"))
      (node (ref "D10") (pin "1") (pinfunction "A_1") (pintype "passive"))
      (node (ref "D11") (pin "1") (pinfunction "A_1") (pintype "passive"))
      (node (ref "D12") (pin "1") (pinfunction "A_1") (pintype "passive"))
      (node (ref "D13") (pin "1") (pinfunction "A_1") (pintype "passive"))
      (node (ref "D14") (pin "1") (pinfunction "A_1") (pintype "passive"))
      (node (ref "D15") (pin "1") (pinfunction "A_1") (pintype "passive"))
      (node (ref "D16") (pin "1") (pinfunction "A_1") (pintype "passive"))
      (node (ref "D17") (pin "1") (pinfunction "A_1") (pintype "passive"))
      (node (ref "D18") (pin "1") (pinfunction "A_1") (pintype "passive"))
      (node (ref "D19") (pin "1") (pinfunction "A_1") (pintype "passive"))
      (node (ref "D2") (pin "1") (pinfunction "A_1") (pintype "passive"))
      (node (ref "D20") (pin "1") (pinfunction "A_1") (pintype "passive"))
      (node (ref "D21") (pin "1") (pinfunction "A_1") (pintype "passive"))
      (node (ref "D22") (pin "1") (pinfunction "A_1") (pintype "passive"))
      (node (ref "D23") (pin "1") (pinfunction "A_1") (pintype "passive"))
      (node (ref "D26") (pin "1") (pinfunction "A_1") (pintype "passive"))
      (node (ref "D27") (pin "1") (pinfunction "A_1") (pintype "passive"))
      (node (ref "D28") (pin "1") (pinfunction "A_1") (pintype "passive"))
      (node (ref "D29") (pin "1") (pinfunction "A_1") (pintype "passive"))
      (node (ref "D3") (pin "1") (pinfunction "A_1") (pintype "passive"))
      (node (ref "D32") (pin "1") (pinfunction "A_1") (pintype "passive"))
      (node (ref "D4") (pin "1") (pinfunction "A_1") (pintype "passive"))
      (node (ref "D5") (pin "1") (pinfunction "A_1") (pintype "passive"))
      (node (ref "D6") (pin "1") (pinfunction "A_1") (pintype "passive"))
      (node (ref "D7") (pin "1") (pinfunction "A_1") (pintype "passive"))
      (node (ref "D8") (pin "1") (pinfunction "A_1") (pintype "passive"))
      (node (ref "D9") (pin "1") (pinfunction "A_1") (pintype "passive"))
      (node (ref "IR") (pin "3") (pinfunction "3_3") (pintype "passive"))
      (node (ref "J1") (pin "GND") (pinfunction "GND_GND") (pintype "bidirectional"))
      (node (ref "J1") (pin "GNDBREAK") (pinfunction "GNDBREAK_GNDBREAK") (pintype "bidirectional"))
      (node (ref "JP10") (pin "5") (pinfunction "5_5") (pintype "bidirectional"))
      (node (ref "JP10") (pin "6") (pinfunction "6_6") (pintype "bidirectional"))
      (node (ref "JP11") (pin "5") (pinfunction "5_5") (pintype "bidirectional"))
      (node (ref "JP11") (pin "6") (pinfunction "6_6") (pintype "bidirectional"))
      (node (ref "JP2") (pin "7") (pinfunction "7_7") (pintype "passive"))
      (node (ref "JP4") (pin "4") (pinfunction "4_4") (pintype "passive"))
      (node (ref "JP4") (pin "5") (pinfunction "5_5") (pintype "passive"))
      (node (ref "JP7") (pin "1") (pinfunction "1_1") (pintype "passive"))
      (node (ref "JP7") (pin "2") (pinfunction "2_2") (pintype "passive"))
      (node (ref "JP7") (pin "3") (pinfunction "3_3") (pintype "passive"))
      (node (ref "JP7") (pin "4") (pinfunction "4_4") (pintype "passive"))
      (node (ref "JP8") (pin "6") (pinfunction "6_6") (pintype "bidirectional"))
      (node (ref "JP9") (pin "GND") (pinfunction "GND_GND") (pintype "bidirectional"))
      (node (ref "POWER") (pin "P$2") (pinfunction "P$2_P$2") (pintype "bidirectional"))
      (node (ref "R26") (pin "1") (pinfunction "1_1") (pintype "passive"))
      (node (ref "R28") (pin "1") (pinfunction "1_1") (pintype "passive"))
      (node (ref "R31") (pin "1") (pinfunction "1_1") (pintype "passive"))
      (node (ref "R34") (pin "1") (pinfunction "1_1") (pintype "passive"))
      (node (ref "R36") (pin "1") (pinfunction "1_1") (pintype "passive"))
      (node (ref "R41") (pin "1") (pinfunction "1_1") (pintype "passive"))
      (node (ref "R46") (pin "1") (pinfunction "1_1") (pintype "passive"))
      (node (ref "R51") (pin "1") (pinfunction "1_1") (pintype "passive"))
      (node (ref "R52") (pin "1") (pinfunction "1_1") (pintype "passive"))
      (node (ref "R53") (pin "1") (pinfunction "1_1") (pintype "passive"))
      (node (ref "R54") (pin "1") (pinfunction "1_1") (pintype "passive"))
      (node (ref "R60") (pin "1") (pinfunction "1_1") (pintype "passive"))
      (node (ref "R62") (pin "1") (pinfunction "1_1") (pintype "passive"))
      (node (ref "RESET") (pin "1") (pinfunction "1_1") (pintype "passive"))
      (node (ref "RESET") (pin "2") (pinfunction "2_2") (pintype "passive"))
      (node (ref "S2") (pin "1") (pinfunction "1_1") (pintype "passive"))
      (node (ref "S2") (pin "2") (pinfunction "2_2") (pintype "passive"))
      (node (ref "U$1") (pin "1") (pinfunction "1_1") (pintype "passive"))
      (node (ref "U$1") (pin "3") (pinfunction "3_3") (pintype "passive"))
      (node (ref "U$1") (pin "7") (pinfunction "7_7") (pintype "passive"))
      (node (ref "U$2") (pin "3") (pinfunction "E_3") (pintype "passive"))
      (node (ref "U$8") (pin "P$10") (pinfunction "GND2_P$10") (pintype "bidirectional"))
      (node (ref "U$8") (pin "P$12") (pinfunction "GND3_P$12") (pintype "bidirectional"))
      (node (ref "U$8") (pin "P$13") (pinfunction "NC3_P$13") (pintype "bidirectional"))
      (node (ref "U$8") (pin "P$5") (pinfunction "GND1_P$5") (pintype "bidirectional"))
      (node (ref "U$8") (pin "P$7") (pinfunction "SA0_P$7") (pintype "bidirectional"))
      (node (ref "U$8") (pin "P$8") (pinfunction "NC2_P$8") (pintype "bidirectional"))
      (node (ref "U1") (pin "18") (pinfunction "GND2_18") (pintype "power_in"))
      (node (ref "U1") (pin "21") (pinfunction "GND3_21") (pintype "power_in"))
      (node (ref "U1") (pin "25") (pinfunction "AGND_25") (pintype "power_in"))
      (node (ref "U1") (pin "26") (pinfunction "TEST_26") (pintype "input"))
      (node (ref "U1") (pin "7") (pinfunction "GND1_7") (pintype "power_in"))
      (node (ref "U10") (pin "GND") (pinfunction "GND_PPAD_GND") (pintype "bidirectional"))
      (node (ref "U10") (pin "P$5") (pinfunction "GND1_P$5") (pintype "bidirectional"))
      (node (ref "U10") (pin "P$6") (pinfunction "GND2_P$6") (pintype "bidirectional"))
      (node (ref "U11") (pin "4") (pinfunction "V-_4") (pintype "power_in"))
      (node (ref "U12") (pin "4") (pinfunction "V-_4") (pintype "power_in"))
      (node (ref "U16") (pin "4") (pinfunction "V-_4") (pintype "power_in"))
      (node (ref "U16") (pin "5") (pinfunction "+IN_5") (pintype "input"))
      (node (ref "U16") (pin "6") (pinfunction "-IN_6") (pintype "input"))
      (node (ref "U17") (pin "22") (pinfunction "GND1_22") (pintype "bidirectional"))
      (node (ref "U17") (pin "53") (pinfunction "GND2_53") (pintype "bidirectional"))
      (node (ref "U17") (pin "63") (pinfunction "GND3_63") (pintype "bidirectional"))
      (node (ref "U3") (pin "2") (pinfunction "GND_2") (pintype "input"))
      (node (ref "U4") (pin "13") (pinfunction "GND_13") (pintype "bidirectional"))
      (node (ref "U4") (pin "21") (pinfunction "GND1_21") (pintype "bidirectional"))
      (node (ref "U4") (pin "22") (pinfunction "GND2_22") (pintype "bidirectional"))
      (node (ref "U4") (pin "34") (pinfunction "PIO11_34") (pintype "bidirectional"))
      (node (ref "U7") (pin "P$2") (pinfunction "GND_P$2") (pintype "bidirectional"))
      (node (ref "U8") (pin "P$2") (pinfunction "GND_P$2") (pintype "bidirectional"))
      (node (ref "U9") (pin "GND") (pinfunction "GND_PPAD_GND") (pintype "bidirectional"))
      (node (ref "U9") (pin "P$5") (pinfunction "GND1_P$5") (pintype "bidirectional"))
      (node (ref "U9") (pin "P$6") (pinfunction "GND2_P$6") (pintype "bidirectional"))
    )
    (net (code "57") (name "/HIGH_5V_REG") (class "Default")
      (node (ref "U3") (pin "5") (pinfunction "OUT_5") (pintype "passive"))
      (node (ref "U6") (pin "S1") (pinfunction "S1_S1") (pintype "bidirectional"))
    )
    (net (code "58") (name "/IR") (class "Default")
      (node (ref "IR") (pin "1") (pinfunction "1_1") (pintype "passive"))
      (node (ref "U17") (pin "25") (pinfunction "PD0_25") (pintype "bidirectional"))
    )
    (net (code "59") (name "/LCD0") (class "Default")
      (node (ref "U$1") (pin "9") (pinfunction "9_9") (pintype "passive"))
      (node (ref "U17") (pin "51") (pinfunction "PA0_51") (pintype "bidirectional"))
    )
    (net (code "60") (name "/LCD1") (class "Default")
      (node (ref "U$1") (pin "10") (pinfunction "10_10") (pintype "passive"))
      (node (ref "U17") (pin "50") (pinfunction "PA1_50") (pintype "bidirectional"))
    )
    (net (code "61") (name "/LCD2") (class "Default")
      (node (ref "U$1") (pin "11") (pinfunction "11_11") (pintype "passive"))
      (node (ref "U17") (pin "49") (pinfunction "PA2_49") (pintype "bidirectional"))
    )
    (net (code "62") (name "/LCD3") (class "Default")
      (node (ref "U$1") (pin "12") (pinfunction "12_12") (pintype "passive"))
      (node (ref "U17") (pin "48") (pinfunction "PA3_48") (pintype "bidirectional"))
    )
    (net (code "63") (name "/LCD4") (class "Default")
      (node (ref "U$1") (pin "13") (pinfunction "13_13") (pintype "passive"))
      (node (ref "U17") (pin "47") (pinfunction "PA4_47") (pintype "bidirectional"))
    )
    (net (code "64") (name "/LCD5") (class "Default")
      (node (ref "U$1") (pin "14") (pinfunction "14_14") (pintype "passive"))
      (node (ref "U17") (pin "46") (pinfunction "PA5_46") (pintype "bidirectional"))
    )
    (net (code "65") (name "/LCD6") (class "Default")
      (node (ref "U$1") (pin "15") (pinfunction "15_15") (pintype "passive"))
      (node (ref "U17") (pin "45") (pinfunction "PA6_45") (pintype "bidirectional"))
    )
    (net (code "66") (name "/LCD7") (class "Default")
      (node (ref "U$1") (pin "16") (pinfunction "16_16") (pintype "passive"))
      (node (ref "U17") (pin "44") (pinfunction "PA7_44") (pintype "bidirectional"))
    )
    (net (code "67") (name "/LED0") (class "Default")
      (node (ref "D30") (pin "A") (pinfunction "A_A") (pintype "passive"))
      (node (ref "U17") (pin "33") (pinfunction "PG0_33") (pintype "bidirectional"))
    )
    (net (code "68") (name "/LED1") (class "Default")
      (node (ref "D31") (pin "A") (pinfunction "A_A") (pintype "passive"))
      (node (ref "U17") (pin "34") (pinfunction "PG1_34") (pintype "bidirectional"))
    )
    (net (code "69") (name "/M0_DIR0") (class "Default")
      (node (ref "U17") (pin "29") (pinfunction "PD4_29") (pintype "bidirectional"))
      (node (ref "U9") (pin "P$9") (pinfunction "IN1_P$9") (pintype "bidirectional"))
    )
    (net (code "70") (name "/M0_DIR1") (class "Default")
      (node (ref "U17") (pin "30") (pinfunction "PD5_30") (pintype "bidirectional"))
      (node (ref "U9") (pin "P$11") (pinfunction "IN2_P$11") (pintype "bidirectional"))
    )
    (net (code "71") (name "/M0_EN") (class "Default")
      (node (ref "U17") (pin "14") (pinfunction "PB4(OC0A)_14") (pintype "bidirectional"))
      (node (ref "U9") (pin "P$10") (pinfunction "EN1_P$10") (pintype "bidirectional"))
      (node (ref "U9") (pin "P$12") (pinfunction "EN2_P$12") (pintype "bidirectional"))
    )
    (net (code "72") (name "/M1_DIR0") (class "Default")
      (node (ref "U10") (pin "P$9") (pinfunction "IN1_P$9") (pintype "bidirectional"))
      (node (ref "U17") (pin "31") (pinfunction "PD6_31") (pintype "bidirectional"))
    )
    (net (code "73") (name "/M1_DIR1") (class "Default")
      (node (ref "U10") (pin "P$11") (pinfunction "IN2_P$11") (pintype "bidirectional"))
      (node (ref "U17") (pin "32") (pinfunction "PD7_32") (pintype "bidirectional"))
    )
    (net (code "74") (name "/M1_EN") (class "Default")
      (node (ref "U10") (pin "P$10") (pinfunction "EN1_P$10") (pintype "bidirectional"))
      (node (ref "U10") (pin "P$12") (pinfunction "EN2_P$12") (pintype "bidirectional"))
      (node (ref "U17") (pin "17") (pinfunction "PB7(OC2A)_17") (pintype "bidirectional"))
    )
    (net (code "75") (name "/MISO") (class "Default")
      (node (ref "D5") (pin "3") (pinfunction "C_3") (pintype "passive"))
      (node (ref "R5") (pin "1") (pinfunction "1_1") (pintype "passive"))
      (node (ref "U17") (pin "13") (pinfunction "PB3(MISO)_13") (pintype "bidirectional"))
    )
    (net (code "76") (name "/MOSI") (class "Default")
      (node (ref "D4") (pin "3") (pinfunction "C_3") (pintype "passive"))
      (node (ref "R4") (pin "1") (pinfunction "1_1") (pintype "passive"))
      (node (ref "U17") (pin "12") (pinfunction "PB2(MOSI)_12") (pintype "bidirectional"))
    )
    (net (code "77") (name "/N$33") (class "Default")
      (node (ref "F1") (pin "2") (pinfunction "2_2") (pintype "passive"))
      (node (ref "JP4") (pin "6") (pinfunction "6_6") (pintype "passive"))
      (node (ref "Q1") (pin "3") (pinfunction "D_3") (pintype "bidirectional"))
    )
    (net (code "78") (name "/PWR_SW") (class "Default")
      (node (ref "D33") (pin "1") (pinfunction "A1_1") (pintype "passive"))
      (node (ref "Q1") (pin "2") (pinfunction "S_2") (pintype "bidirectional"))
      (node (ref "Q2") (pin "2") (pinfunction "S_2") (pintype "bidirectional"))
      (node (ref "R44") (pin "1") (pinfunction "1_1") (pintype "passive"))
      (node (ref "U2") (pin "S2") (pinfunction "S2_S2") (pintype "bidirectional"))
    )
    (net (code "79") (name "/RESET") (class "Default")
      (node (ref "C4") (pin "2") (pinfunction "2_2") (pintype "passive"))
      (node (ref "R39") (pin "1") (pinfunction "1_1") (pintype "passive"))
      (node (ref "R40") (pin "2") (pinfunction "2_2") (pintype "passive"))
      (node (ref "R56") (pin "1") (pinfunction "1_1") (pintype "passive"))
      (node (ref "RESET") (pin "3") (pinfunction "3_3") (pintype "passive"))
      (node (ref "RESET") (pin "4") (pinfunction "4_4") (pintype "passive"))
      (node (ref "U17") (pin "20") (pinfunction "RESET/PG5_20") (pintype "bidirectional"))
    )
    (net (code "80") (name "/RS") (class "Default")
      (node (ref "U$1") (pin "6") (pinfunction "6_6") (pintype "passive"))
      (node (ref "U17") (pin "36") (pinfunction "PC1_36") (pintype "bidirectional"))
    )
    (net (code "81") (name "/RX") (class "Default")
      (node (ref "U1") (pin "1") (pinfunction "TXD_1") (pintype "output"))
      (node (ref "U17") (pin "28") (pinfunction "PD3_28") (pintype "bidirectional"))
    )
    (net (code "82") (name "/SCK") (class "Default")
      (node (ref "D6") (pin "3") (pinfunction "C_3") (pintype "passive"))
      (node (ref "R6") (pin "1") (pinfunction "1_1") (pintype "passive"))
      (node (ref "U17") (pin "11") (pinfunction "PB1(SCK)_11") (pintype "bidirectional"))
    )
    (net (code "83") (name "/SCL0") (class "Default")
      (node (ref "JP2") (pin "9") (pinfunction "9_9") (pintype "passive"))
      (node (ref "R7") (pin "2") (pinfunction "2_2") (pintype "passive"))
    )
    (net (code "84") (name "/SCL_IN") (class "Default")
      (node (ref "D7") (pin "3") (pinfunction "C_3") (pintype "passive"))
      (node (ref "R38") (pin "1") (pinfunction "1_1") (pintype "passive"))
      (node (ref "R7") (pin "1") (pinfunction "1_1") (pintype "passive"))
      (node (ref "U$8") (pin "P$4") (pinfunction "SCL_P$4") (pintype "bidirectional"))
      (node (ref "U17") (pin "6") (pinfunction "PE4(SCL)_6") (pintype "bidirectional"))
    )
    (net (code "85") (name "/SDA0") (class "Default")
      (node (ref "JP2") (pin "10") (pinfunction "10_10") (pintype "passive"))
      (node (ref "R8") (pin "2") (pinfunction "2_2") (pintype "passive"))
    )
    (net (code "86") (name "/SDA_IN") (class "Default")
      (node (ref "D8") (pin "3") (pinfunction "C_3") (pintype "passive"))
      (node (ref "R37") (pin "1") (pinfunction "1_1") (pintype "passive"))
      (node (ref "R8") (pin "1") (pinfunction "1_1") (pintype "passive"))
      (node (ref "U$8") (pin "P$6") (pinfunction "SDA_P$6") (pintype "bidirectional"))
      (node (ref "U17") (pin "7") (pinfunction "PE5(SDA)_7") (pintype "bidirectional"))
    )
    (net (code "87") (name "/SERVO0") (class "Default")
      (node (ref "JP3") (pin "1") (pinfunction "1_1") (pintype "passive"))
      (node (ref "R47") (pin "2") (pinfunction "2_2") (pintype "passive"))
    )
    (net (code "88") (name "/SERVO0_IN") (class "Default")
      (node (ref "D26") (pin "3") (pinfunction "C_3") (pintype "passive"))
      (node (ref "R47") (pin "1") (pinfunction "1_1") (pintype "passive"))
      (node (ref "U17") (pin "37") (pinfunction "PC2_37") (pintype "bidirectional"))
    )
    (net (code "89") (name "/SERVO1") (class "Default")
      (node (ref "JP3") (pin "2") (pinfunction "2_2") (pintype "passive"))
      (node (ref "R48") (pin "2") (pinfunction "2_2") (pintype "passive"))
    )
    (net (code "90") (name "/SERVO1_IN") (class "Default")
      (node (ref "D27") (pin "3") (pinfunction "C_3") (pintype "passive"))
      (node (ref "R48") (pin "1") (pinfunction "1_1") (pintype "passive"))
      (node (ref "U17") (pin "38") (pinfunction "PC3_38") (pintype "bidirectional"))
    )
    (net (code "91") (name "/SERVO2") (class "Default")
      (node (ref "JP3") (pin "3") (pinfunction "3_3") (pintype "passive"))
      (node (ref "R49") (pin "2") (pinfunction "2_2") (pintype "passive"))
    )
    (net (code "92") (name "/SERVO2_IN") (class "Default")
      (node (ref "D28") (pin "3") (pinfunction "C_3") (pintype "passive"))
      (node (ref "R49") (pin "1") (pinfunction "1_1") (pintype "passive"))
      (node (ref "U17") (pin "39") (pinfunction "PC4_39") (pintype "bidirectional"))
    )
    (net (code "93") (name "/SERVO3") (class "Default")
      (node (ref "JP3") (pin "4") (pinfunction "4_4") (pintype "passive"))
      (node (ref "R50") (pin "2") (pinfunction "2_2") (pintype "passive"))
    )
    (net (code "94") (name "/SERVO3_IN") (class "Default")
      (node (ref "D29") (pin "3") (pinfunction "C_3") (pintype "passive"))
      (node (ref "R50") (pin "1") (pinfunction "1_1") (pintype "passive"))
      (node (ref "U17") (pin "54") (pinfunction "PF7(ADC7)_54") (pintype "bidirectional"))
    )
    (net (code "95") (name "/SS") (class "Default")
      (node (ref "D3") (pin "3") (pinfunction "C_3") (pintype "passive"))
      (node (ref "R3") (pin "1") (pinfunction "1_1") (pintype "passive"))
      (node (ref "U17") (pin "10") (pinfunction "PB0(SS)_10") (pintype "bidirectional"))
    )
    (net (code "96") (name "/SW1") (class "Default")
      (node (ref "S2") (pin "3") (pinfunction "3_3") (pintype "passive"))
      (node (ref "S2") (pin "4") (pinfunction "4_4") (pintype "passive"))
      (node (ref "U17") (pin "9") (pinfunction "PE7_9") (pintype "bidirectional"))
    )
    (net (code "97") (name "/TX") (class "Default")
      (node (ref "U1") (pin "5") (pinfunction "RXD_5") (pintype "input"))
      (node (ref "U17") (pin "27") (pinfunction "PD2_27") (pintype "bidirectional"))
    )
    (net (code "98") (name "/USBGATE") (class "Default")
      (node (ref "R42") (pin "1") (pinfunction "1_1") (pintype "passive"))
      (node (ref "R60") (pin "2") (pinfunction "2_2") (pintype "passive"))
      (node (ref "U16") (pin "1") (pinfunction "OUT_1") (pintype "output"))
      (node (ref "U2") (pin "G1") (pinfunction "G1_G1") (pintype "bidirectional"))
      (node (ref "U2") (pin "G2") (pinfunction "G2_G2") (pintype "bidirectional"))
    )
    (net (code "99") (name "/USB_5V") (class "Default")
      (node (ref "D33") (pin "2") (pinfunction "A2_2") (pintype "passive"))
      (node (ref "F2") (pin "2") (pinfunction "2_2") (pintype "passive"))
      (node (ref "R54") (pin "2") (pinfunction "2_2") (pintype "passive"))
      (node (ref "R55") (pin "1") (pinfunction "1_1") (pintype "passive"))
      (node (ref "U1") (pin "20") (pinfunction "VCC_20") (pintype "power_in"))
      (node (ref "U1") (pin "4") (pinfunction "VCCIO_4") (pintype "power_in"))
      (node (ref "U16") (pin "8") (pinfunction "V+_8") (pintype "power_in"))
      (node (ref "U2") (pin "S1") (pinfunction "S1_S1") (pintype "bidirectional"))
    )
    (net (code "100") (name "/VIN") (class "Default")
      (node (ref "F1") (pin "1") (pinfunction "1_1") (pintype "passive"))
      (node (ref "J1") (pin "PWR") (pinfunction "PWR_PWR") (pintype "bidirectional"))
      (node (ref "R35") (pin "2") (pinfunction "2_2") (pintype "passive"))
    )
    (net (code "101") (name "/VIN_F") (class "Default")
      (node (ref "JP6") (pin "1") (pinfunction "1_1") (pintype "passive"))
      (node (ref "JP6") (pin "2") (pinfunction "2_2") (pintype "passive"))
      (node (ref "JP6") (pin "3") (pinfunction "3_3") (pintype "passive"))
      (node (ref "JP6") (pin "4") (pinfunction "4_4") (pintype "passive"))
      (node (ref "Q2") (pin "3") (pinfunction "D_3") (pintype "bidirectional"))
      (node (ref "R29") (pin "2") (pinfunction "2_2") (pintype "passive"))
      (node (ref "R32") (pin "2") (pinfunction "2_2") (pintype "passive"))
      (node (ref "R33") (pin "2") (pinfunction "2_2") (pintype "passive"))
      (node (ref "R45") (pin "2") (pinfunction "2_2") (pintype "passive"))
      (node (ref "U10") (pin "P$1") (pinfunction "VM1_P$1") (pintype "bidirectional"))
      (node (ref "U10") (pin "P$2") (pinfunction "VM2_P$2") (pintype "bidirectional"))
      (node (ref "U11") (pin "8") (pinfunction "V+_8") (pintype "power_in"))
      (node (ref "U12") (pin "8") (pinfunction "V+_8") (pintype "power_in"))
      (node (ref "U3") (pin "1") (pinfunction "IN_1") (pintype "input"))
      (node (ref "U3") (pin "3") (pinfunction "EN_3") (pintype "input"))
      (node (ref "U5") (pin "S1") (pinfunction "S1_S1") (pintype "bidirectional"))
      (node (ref "U9") (pin "P$1") (pinfunction "VM1_P$1") (pintype "bidirectional"))
      (node (ref "U9") (pin "P$2") (pinfunction "VM2_P$2") (pintype "bidirectional"))
    )
    (net (code "102") (name "Net-(D25-PadC)") (class "Default")
      (node (ref "D25") (pin "C") (pinfunction "C_C") (pintype "passive"))
      (node (ref "R41") (pin "2") (pinfunction "2_2") (pintype "passive"))
    )
    (net (code "103") (name "Net-(D30-PadC)") (class "Default")
      (node (ref "D30") (pin "C") (pinfunction "C_C") (pintype "passive"))
      (node (ref "R51") (pin "2") (pinfunction "2_2") (pintype "passive"))
    )
    (net (code "104") (name "Net-(D31-PadC)") (class "Default")
      (node (ref "D31") (pin "C") (pinfunction "C_C") (pintype "passive"))
      (node (ref "R52") (pin "2") (pinfunction "2_2") (pintype "passive"))
    )
    (net (code "105") (name "Net-(D33-CC)") (class "Default")
      (node (ref "D33") (pin "3") (pinfunction "CC_3") (pintype "passive"))
      (node (ref "R42") (pin "2") (pinfunction "2_2") (pintype "passive"))
    )
    (net (code "106") (name "Net-(D34-PadA)") (class "Default")
      (node (ref "D34") (pin "A") (pinfunction "A_A") (pintype "passive"))
      (node (ref "R57") (pin "2") (pinfunction "2_2") (pintype "passive"))
    )
    (net (code "107") (name "Net-(F2-Pad1)") (class "Default")
      (node (ref "F2") (pin "1") (pinfunction "1_1") (pintype "passive"))
      (node (ref "JP9") (pin "VBUS") (pinfunction "VBUS_VBUS") (pintype "bidirectional"))
    )
    (net (code "108") (name "Net-(JP4-Pad1)") (class "Default")
      (node (ref "JP4") (pin "1") (pinfunction "1_1") (pintype "passive"))
      (node (ref "R56") (pin "2") (pinfunction "2_2") (pintype "passive"))
    )
    (net (code "109") (name "Net-(JP8-Pad5)") (class "Default")
      (node (ref "JP8") (pin "5") (pinfunction "5_5") (pintype "bidirectional"))
      (node (ref "R39") (pin "2") (pinfunction "2_2") (pintype "passive"))
    )
    (net (code "110") (name "Net-(POWER-PadP$1)") (class "Default")
      (node (ref "POWER") (pin "P$1") (pinfunction "P$1_P$1") (pintype "bidirectional"))
      (node (ref "R43") (pin "2") (pinfunction "2_2") (pintype "passive"))
    )
    (net (code "111") (name "Net-(Q1-G)") (class "Default")
      (node (ref "Q1") (pin "1") (pinfunction "G_1") (pintype "bidirectional"))
      (node (ref "R34") (pin "2") (pinfunction "2_2") (pintype "passive"))
    )
    (net (code "112") (name "Net-(Q2-G)") (class "Default")
      (node (ref "Q2") (pin "1") (pinfunction "G_1") (pintype "bidirectional"))
      (node (ref "R43") (pin "1") (pinfunction "1_1") (pintype "passive"))
      (node (ref "R44") (pin "2") (pinfunction "2_2") (pintype "passive"))
    )
    (net (code "113") (name "Net-(Q3-G)") (class "Default")
      (node (ref "Q3") (pin "1") (pinfunction "G_1") (pintype "bidirectional"))
      (node (ref "R25") (pin "1") (pinfunction "1_1") (pintype "passive"))
      (node (ref "U12") (pin "7") (pinfunction "OUT_7") (pintype "output"))
    )
    (net (code "114") (name "Net-(Q4-G)") (class "Default")
      (node (ref "Q4") (pin "1") (pinfunction "G_1") (pintype "bidirectional"))
      (node (ref "R30") (pin "1") (pinfunction "1_1") (pintype "passive"))
      (node (ref "U12") (pin "1") (pinfunction "OUT_1") (pintype "output"))
    )
    (net (code "115") (name "Net-(R64-Pad2)") (class "Default")
      (node (ref "R64") (pin "2") (pinfunction "2_2") (pintype "passive"))
      (node (ref "U$1") (pin "2") (pinfunction "2_2") (pintype "passive"))
    )
    (net (code "116") (name "Net-(U$2-S)") (class "Default")
      (node (ref "U$1") (pin "5") (pinfunction "5_5") (pintype "passive"))
      (node (ref "U$2") (pin "2") (pinfunction "S_2") (pintype "passive"))
    )
    (net (code "117") (name "Net-(U$8-BYP)") (class "Default")
      (node (ref "C5") (pin "1") (pinfunction "1_1") (pintype "passive"))
      (node (ref "U$8") (pin "P$2") (pinfunction "BYP_P$2") (pintype "bidirectional"))
    )
    (net (code "118") (name "Net-(U1-DTR)") (class "Default")
      (node (ref "R63") (pin "2") (pinfunction "2_2") (pintype "passive"))
      (node (ref "U1") (pin "2") (pinfunction "DTR_2") (pintype "bidirectional"))
    )
    (net (code "119") (name "Net-(U1-RXLED)") (class "Default")
      (node (ref "D34") (pin "C") (pinfunction "C_C") (pintype "passive"))
      (node (ref "U1") (pin "22") (pinfunction "RXLED_22") (pintype "bidirectional"))
    )
    (net (code "120") (name "Net-(U1-USBDM)") (class "Default")
      (node (ref "JP9") (pin "D-") (pinfunction "D-_D-") (pintype "bidirectional"))
      (node (ref "U1") (pin "16") (pinfunction "USBDM_16") (pintype "bidirectional"))
    )
    (net (code "121") (name "Net-(U1-USBDP)") (class "Default")
      (node (ref "JP9") (pin "D+") (pinfunction "D+_D+") (pintype "bidirectional"))
      (node (ref "U1") (pin "15") (pinfunction "USBDP_15") (pintype "bidirectional"))
    )
    (net (code "122") (name "Net-(U2-D1-PadD1@)") (class "Default")
      (node (ref "U2") (pin "D1") (pinfunction "D1_D1") (pintype "bidirectional"))
      (node (ref "U2") (pin "D1@") (pinfunction "D1_D1@") (pintype "bidirectional"))
      (node (ref "U2") (pin "D2") (pinfunction "D2_D2") (pintype "bidirectional"))
      (node (ref "U2") (pin "D2@") (pinfunction "D2_D2@") (pintype "bidirectional"))
    )
    (net (code "123") (name "Net-(U4-RX)") (class "Default")
      (node (ref "R61") (pin "1") (pinfunction "1_1") (pintype "passive"))
      (node (ref "R62") (pin "2") (pinfunction "2_2") (pintype "passive"))
      (node (ref "U4") (pin "2") (pinfunction "RX_2") (pintype "bidirectional"))
    )
    (net (code "124") (name "Net-(U5-D1-PadD1@)") (class "Default")
      (node (ref "U5") (pin "D1") (pinfunction "D1_D1") (pintype "bidirectional"))
      (node (ref "U5") (pin "D1@") (pinfunction "D1_D1@") (pintype "bidirectional"))
      (node (ref "U5") (pin "D2") (pinfunction "D2_D2") (pintype "bidirectional"))
      (node (ref "U5") (pin "D2@") (pinfunction "D2_D2@") (pintype "bidirectional"))
    )
    (net (code "125") (name "Net-(U6-D1-PadD1@)") (class "Default")
      (node (ref "U6") (pin "D1") (pinfunction "D1_D1") (pintype "bidirectional"))
      (node (ref "U6") (pin "D1@") (pinfunction "D1_D1@") (pintype "bidirectional"))
      (node (ref "U6") (pin "D2") (pinfunction "D2_D2") (pintype "bidirectional"))
      (node (ref "U6") (pin "D2@") (pinfunction "D2_D2@") (pintype "bidirectional"))
    )
    (net (code "126") (name "Net-(U8-ILIM)") (class "Default")
      (node (ref "R53") (pin "2") (pinfunction "2_2") (pintype "passive"))
      (node (ref "U8") (pin "P$5") (pinfunction "ILIM_P$5") (pintype "bidirectional"))
    )
    (net (code "127") (name "Net-(U11A-+IN)") (class "Default")
      (node (ref "R28") (pin "2") (pinfunction "2_2") (pintype "passive"))
      (node (ref "R29") (pin "1") (pinfunction "1_1") (pintype "passive"))
      (node (ref "R58") (pin "2") (pinfunction "2_2") (pintype "passive"))
      (node (ref "U11") (pin "3") (pinfunction "+IN_3") (pintype "input"))
    )
    (net (code "128") (name "Net-(U12A-+IN)") (class "Default")
      (node (ref "R27") (pin "1") (pinfunction "1_1") (pintype "passive"))
      (node (ref "R31") (pin "2") (pinfunction "2_2") (pintype "passive"))
      (node (ref "U12") (pin "3") (pinfunction "+IN_3") (pintype "input"))
    )
    (net (code "129") (name "Net-(U12B-+IN)") (class "Default")
      (node (ref "R24") (pin "1") (pinfunction "1_1") (pintype "passive"))
      (node (ref "R26") (pin "2") (pinfunction "2_2") (pintype "passive"))
      (node (ref "U12") (pin "5") (pinfunction "+IN_5") (pintype "input"))
    )
    (net (code "130") (name "Net-(U16A-+IN)") (class "Default")
      (node (ref "R35") (pin "1") (pinfunction "1_1") (pintype "passive"))
      (node (ref "R36") (pin "2") (pinfunction "2_2") (pintype "passive"))
      (node (ref "U16") (pin "3") (pinfunction "+IN_3") (pintype "input"))
    )
    (net (code "131") (name "Net-(U17-PF6(ADC6))") (class "Default")
      (node (ref "R45") (pin "1") (pinfunction "1_1") (pintype "passive"))
      (node (ref "R46") (pin "2") (pinfunction "2_2") (pintype "passive"))
      (node (ref "U17") (pin "55") (pinfunction "PF6(ADC6)_55") (pintype "bidirectional"))
    )
    (net (code "132") (name "Net-(U17-PG2)") (class "Default")
      (node (ref "R55") (pin "2") (pinfunction "2_2") (pintype "passive"))
      (node (ref "U17") (pin "43") (pinfunction "PG2_43") (pintype "bidirectional"))
    )
    (net (code "133") (name "Net-(U17-XTAL1)") (class "Default")
      (node (ref "C1") (pin "2") (pinfunction "2_2") (pintype "passive"))
      (node (ref "U17") (pin "24") (pinfunction "XTAL1_24") (pintype "bidirectional"))
      (node (ref "Y1") (pin "P$1") (pinfunction "1_P$1") (pintype "passive"))
    )
    (net (code "134") (name "Net-(U17-XTAL2)") (class "Default")
      (node (ref "C2") (pin "2") (pinfunction "2_2") (pintype "passive"))
      (node (ref "U17") (pin "23") (pinfunction "XTAL2_23") (pintype "bidirectional"))
      (node (ref "Y1") (pin "P$2") (pinfunction "2_P$2") (pintype "passive"))
    )
    (net (code "135") (name "unconnected-(U$8-INT2-PadP$9)") (class "Default")
      (node (ref "U$8") (pin "P$9") (pinfunction "INT2_P$9") (pintype "bidirectional"))
    )
    (net (code "136") (name "unconnected-(U$8-NC1-PadP$3)") (class "Default")
      (node (ref "U$8") (pin "P$3") (pinfunction "NC1_P$3") (pintype "bidirectional"))
    )
    (net (code "137") (name "unconnected-(U1-3V3OUT-Pad17)") (class "Default")
      (node (ref "U1") (pin "17") (pinfunction "3V3OUT_17") (pintype "output"))
    )
    (net (code "138") (name "unconnected-(U1-CTS-Pad11)") (class "Default")
      (node (ref "U1") (pin "11") (pinfunction "CTS_11") (pintype "bidirectional"))
    )
    (net (code "139") (name "unconnected-(U1-RTS-Pad3)") (class "Default")
      (node (ref "U1") (pin "3") (pinfunction "RTS_3") (pintype "bidirectional"))
    )
    (net (code "140") (name "unconnected-(U1-TXLED-Pad23)") (class "Default")
      (node (ref "U1") (pin "23") (pinfunction "TXLED_23") (pintype "bidirectional"))
    )
    (net (code "141") (name "unconnected-(U3-BP-Pad4)") (class "Default")
      (node (ref "U3") (pin "4") (pinfunction "BP_4") (pintype "input"))
    )
    (net (code "142") (name "unconnected-(U4-AIO0-Pad9)") (class "Default")
      (node (ref "U4") (pin "9") (pinfunction "AIO0_9") (pintype "bidirectional"))
    )
    (net (code "143") (name "unconnected-(U4-AIO1-Pad10)") (class "Default")
      (node (ref "U4") (pin "10") (pinfunction "AIO1_10") (pintype "bidirectional"))
    )
    (net (code "144") (name "unconnected-(U4-CLK-Pad19)") (class "Default")
      (node (ref "U4") (pin "19") (pinfunction "CLK_19") (pintype "bidirectional"))
    )
    (net (code "145") (name "unconnected-(U4-CSB-Pad16)") (class "Default")
      (node (ref "U4") (pin "16") (pinfunction "CSB_16") (pintype "bidirectional"))
    )
    (net (code "146") (name "unconnected-(U4-CTS-Pad3)") (class "Default")
      (node (ref "U4") (pin "3") (pinfunction "CTS_3") (pintype "bidirectional"))
    )
    (net (code "147") (name "unconnected-(U4-MISO-Pad18)") (class "Default")
      (node (ref "U4") (pin "18") (pinfunction "MISO_18") (pintype "bidirectional"))
    )
    (net (code "148") (name "unconnected-(U4-MOSI-Pad17)") (class "Default")
      (node (ref "U4") (pin "17") (pinfunction "MOSI_17") (pintype "bidirectional"))
    )
    (net (code "149") (name "unconnected-(U4-NC-Pad14)") (class "Default")
      (node (ref "U4") (pin "14") (pinfunction "NC_14") (pintype "bidirectional"))
    )
    (net (code "150") (name "unconnected-(U4-PCM_CLK-Pad5)") (class "Default")
      (node (ref "U4") (pin "5") (pinfunction "PCM_CLK_5") (pintype "bidirectional"))
    )
    (net (code "151") (name "unconnected-(U4-PCM_IN-Pad7)") (class "Default")
      (node (ref "U4") (pin "7") (pinfunction "PCM_IN_7") (pintype "bidirectional"))
    )
    (net (code "152") (name "unconnected-(U4-PCM_OUT-Pad6)") (class "Default")
      (node (ref "U4") (pin "6") (pinfunction "PCM_OUT_6") (pintype "bidirectional"))
    )
    (net (code "153") (name "unconnected-(U4-PCN_SYNC-Pad8)") (class "Default")
      (node (ref "U4") (pin "8") (pinfunction "PCN_SYNC_8") (pintype "bidirectional"))
    )
    (net (code "154") (name "unconnected-(U4-PIO0-Pad23)") (class "Default")
      (node (ref "U4") (pin "23") (pinfunction "PIO0_23") (pintype "bidirectional"))
    )
    (net (code "155") (name "unconnected-(U4-PIO1-Pad24)") (class "Default")
      (node (ref "U4") (pin "24") (pinfunction "PIO1_24") (pintype "bidirectional"))
    )
    (net (code "156") (name "unconnected-(U4-PIO2-Pad25)") (class "Default")
      (node (ref "U4") (pin "25") (pinfunction "PIO2_25") (pintype "bidirectional"))
    )
    (net (code "157") (name "unconnected-(U4-PIO3-Pad26)") (class "Default")
      (node (ref "U4") (pin "26") (pinfunction "PIO3_26") (pintype "bidirectional"))
    )
    (net (code "158") (name "unconnected-(U4-PIO4-Pad27)") (class "Default")
      (node (ref "U4") (pin "27") (pinfunction "PIO4_27") (pintype "bidirectional"))
    )
    (net (code "159") (name "unconnected-(U4-PIO5-Pad28)") (class "Default")
      (node (ref "U4") (pin "28") (pinfunction "PIO5_28") (pintype "bidirectional"))
    )
    (net (code "160") (name "unconnected-(U4-PIO6-Pad29)") (class "Default")
      (node (ref "U4") (pin "29") (pinfunction "PIO6_29") (pintype "bidirectional"))
    )
    (net (code "161") (name "unconnected-(U4-PIO7-Pad30)") (class "Default")
      (node (ref "U4") (pin "30") (pinfunction "PIO7_30") (pintype "bidirectional"))
    )
    (net (code "162") (name "unconnected-(U4-PIO8-Pad31)") (class "Default")
      (node (ref "U4") (pin "31") (pinfunction "PIO8_31") (pintype "bidirectional"))
    )
    (net (code "163") (name "unconnected-(U4-PIO9-Pad32)") (class "Default")
      (node (ref "U4") (pin "32") (pinfunction "PIO9_32") (pintype "bidirectional"))
    )
    (net (code "164") (name "unconnected-(U4-PIO10-Pad33)") (class "Default")
      (node (ref "U4") (pin "33") (pinfunction "PIO10_33") (pintype "bidirectional"))
    )
    (net (code "165") (name "unconnected-(U4-RST-Pad11)") (class "Default")
      (node (ref "U4") (pin "11") (pinfunction "RST_11") (pintype "bidirectional"))
    )
    (net (code "166") (name "unconnected-(U4-RTS-Pad4)") (class "Default")
      (node (ref "U4") (pin "4") (pinfunction "RTS_4") (pintype "bidirectional"))
    )
    (net (code "167") (name "unconnected-(U4-VBUSD+-Pad20)") (class "Default")
      (node (ref "U4") (pin "20") (pinfunction "VBUSD+_20") (pintype "bidirectional"))
    )
    (net (code "168") (name "unconnected-(U4-VBUSD--Pad15)") (class "Default")
      (node (ref "U4") (pin "15") (pinfunction "VBUSD-_15") (pintype "bidirectional"))
    )
    (net (code "169") (name "unconnected-(U7-NC-PadP$5)") (class "Default")
      (node (ref "U7") (pin "P$5") (pinfunction "NC_P$5") (pintype "bidirectional"))
    )
    (net (code "170") (name "unconnected-(U8-FAULT-PadP$4)") (class "Default")
      (node (ref "U8") (pin "P$4") (pinfunction "FAULT_P$4") (pintype "bidirectional"))
    )
    (net (code "171") (name "unconnected-(U16B-OUT-Pad7)") (class "Default")
      (node (ref "U16") (pin "7") (pinfunction "OUT_7") (pintype "output"))
    )
    (net (code "172") (name "unconnected-(U17-NC-Pad1)") (class "Default")
      (node (ref "U17") (pin "1") (pinfunction "NC_1") (pintype "bidirectional"))
    )
  )
)
